# Arduino_shield.net
KiCad netlist of a schematic drawn in EAGLE
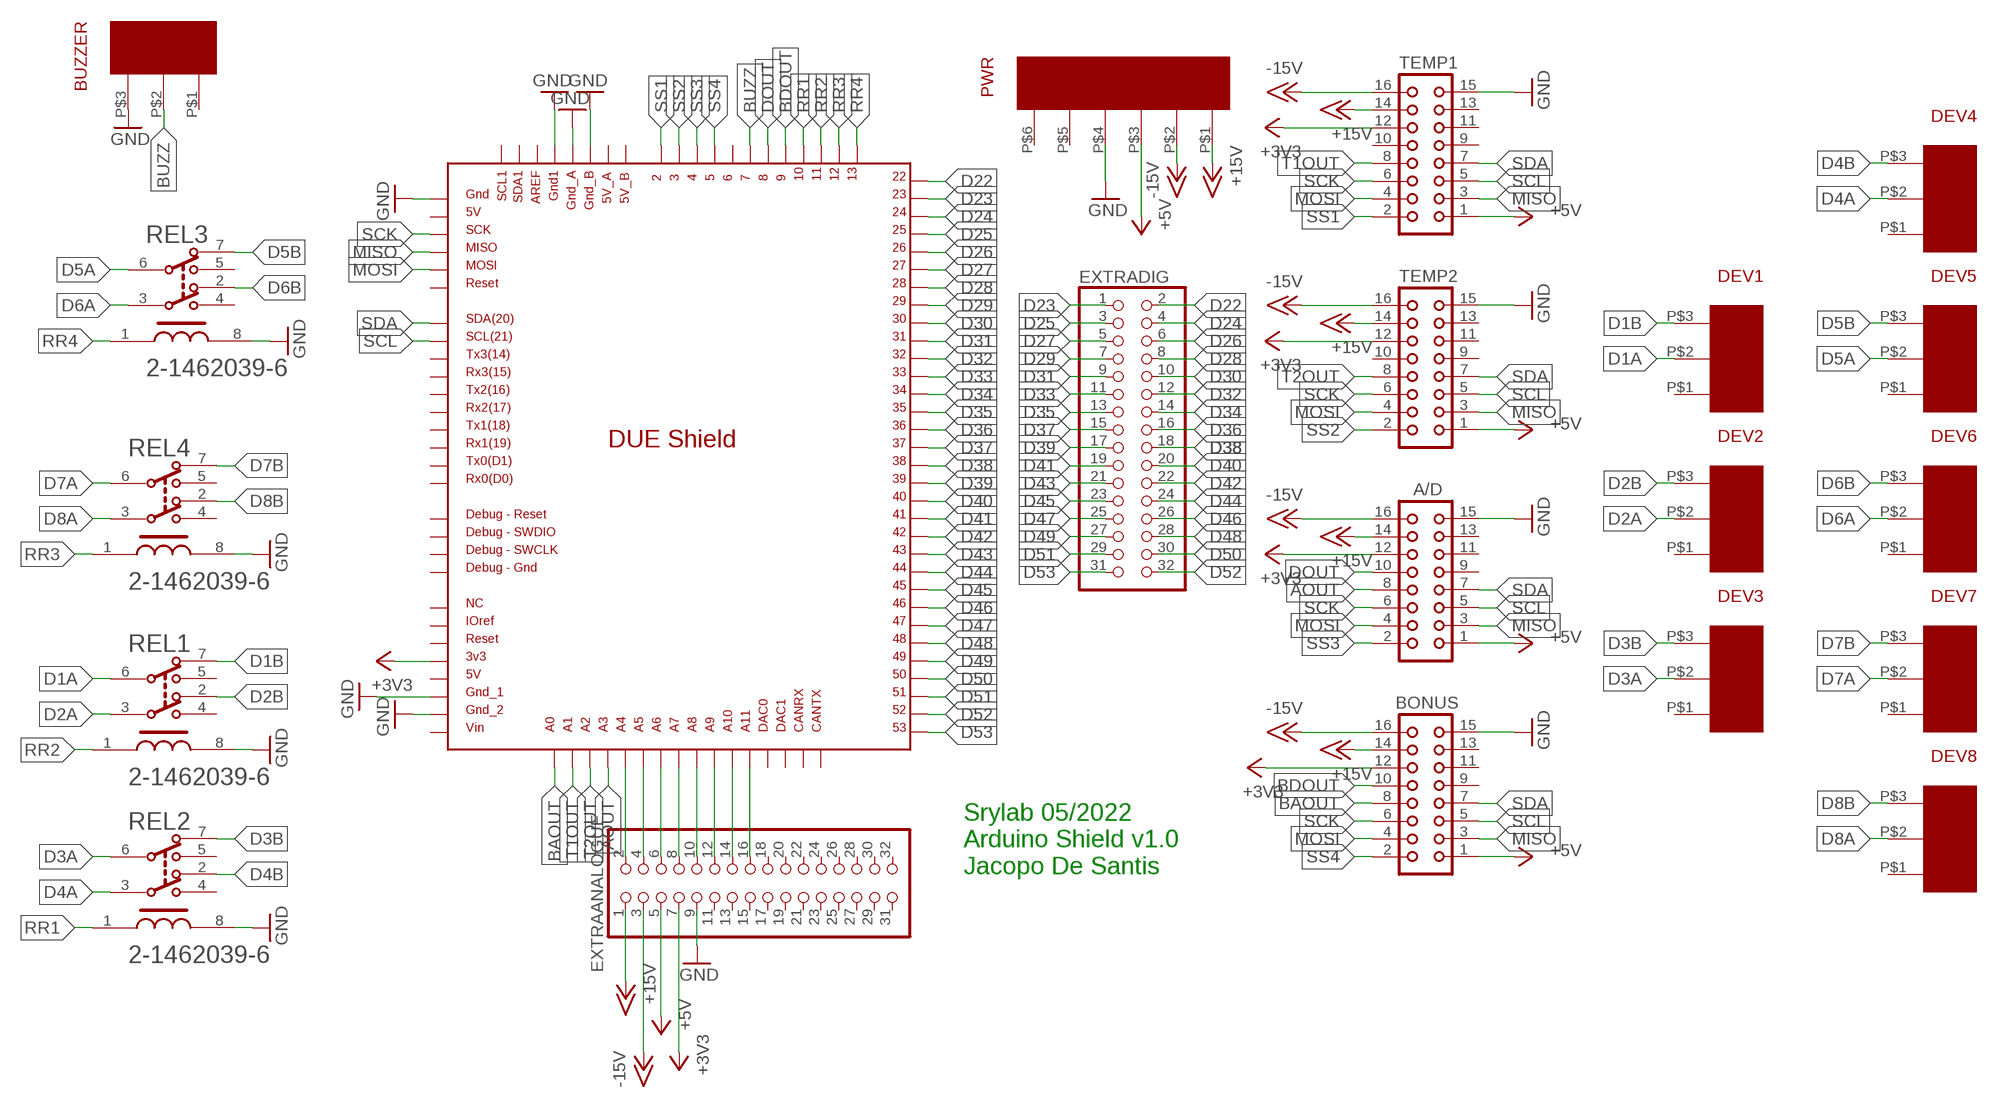
[diagram p0: schematic, sheet 1]

(export (version "E")
  (design (tool "Eeschema 10.0.6"))
  (components
    (comp (ref "A/D")
      (value "CON16L")
      (footprint "eagle-import:CON16L")
      (libsource (lib "eagle-import") (part "CON16L"))
    )
    (comp (ref "BONUS")
      (value "CON16L")
      (footprint "eagle-import:CON16L")
      (libsource (lib "eagle-import") (part "CON16L"))
    )
    (comp (ref "BUZZER")
      (value "3PIN_CON")
      (footprint "eagle-import:3PIN_CON")
      (libsource (lib "eagle-import") (part "3PIN_CON"))
    )
    (comp (ref "DEV1")
      (value "3PIN_CON")
      (footprint "eagle-import:3PIN_CON")
      (libsource (lib "eagle-import") (part "3PIN_CON"))
    )
    (comp (ref "DEV2")
      (value "3PIN_CON")
      (footprint "eagle-import:3PIN_CON")
      (libsource (lib "eagle-import") (part "3PIN_CON"))
    )
    (comp (ref "DEV3")
      (value "3PIN_CON")
      (footprint "eagle-import:3PIN_CON")
      (libsource (lib "eagle-import") (part "3PIN_CON"))
    )
    (comp (ref "DEV4")
      (value "3PIN_CON")
      (footprint "eagle-import:3PIN_CON")
      (libsource (lib "eagle-import") (part "3PIN_CON"))
    )
    (comp (ref "DEV5")
      (value "3PIN_CON")
      (footprint "eagle-import:3PIN_CON")
      (libsource (lib "eagle-import") (part "3PIN_CON"))
    )
    (comp (ref "DEV6")
      (value "3PIN_CON")
      (footprint "eagle-import:3PIN_CON")
      (libsource (lib "eagle-import") (part "3PIN_CON"))
    )
    (comp (ref "DEV7")
      (value "3PIN_CON")
      (footprint "eagle-import:3PIN_CON")
      (libsource (lib "eagle-import") (part "3PIN_CON"))
    )
    (comp (ref "DEV8")
      (value "3PIN_CON")
      (footprint "eagle-import:3PIN_CON")
      (libsource (lib "eagle-import") (part "3PIN_CON"))
    )
    (comp (ref "EXTRAANALOGUE")
      (value "PINHD-2X16")
      (footprint "eagle-import:2X16")
      (libsource (lib "eagle-import") (part "PINHD-2X16"))
    )
    (comp (ref "EXTRADIG")
      (value "PINHD-2X16")
      (footprint "eagle-import:2X16")
      (libsource (lib "eagle-import") (part "PINHD-2X16"))
    )
    (comp (ref "PWR")
      (value "6PIN_CON")
      (footprint "eagle-import:6PIN_CON")
      (libsource (lib "eagle-import") (part "6PIN_CON"))
    )
    (comp (ref "REL1")
      (value "TE_2-1462039-6TE_2-1462039-6_0_0")
      (footprint "eagle-import:TE_2-1462039-6_0")
      (fields
        (field (name "DIGIKEY_PART_NUMBER") "PB1163CT-ND")
        (field (name "MF") "TE")
        (field (name "MOUSER_PART_NUMBER") "655-IM21GR")
      )
      (libsource (lib "eagle-import") (part "TE_2-1462039-6TE_2-1462039-6_0_0"))
    )
    (comp (ref "REL2")
      (value "TE_2-1462039-6TE_2-1462039-6_0_0")
      (footprint "eagle-import:TE_2-1462039-6_0")
      (fields
        (field (name "DIGIKEY_PART_NUMBER") "PB1163CT-ND")
        (field (name "MF") "TE")
        (field (name "MOUSER_PART_NUMBER") "655-IM21GR")
      )
      (libsource (lib "eagle-import") (part "TE_2-1462039-6TE_2-1462039-6_0_0"))
    )
    (comp (ref "REL3")
      (value "TE_2-1462039-6TE_2-1462039-6_0_0")
      (footprint "eagle-import:TE_2-1462039-6_0")
      (fields
        (field (name "DIGIKEY_PART_NUMBER") "PB1163CT-ND")
        (field (name "MF") "TE")
        (field (name "MOUSER_PART_NUMBER") "655-IM21GR")
      )
      (libsource (lib "eagle-import") (part "TE_2-1462039-6TE_2-1462039-6_0_0"))
    )
    (comp (ref "REL4")
      (value "TE_2-1462039-6TE_2-1462039-6_0_0")
      (footprint "eagle-import:TE_2-1462039-6_0")
      (fields
        (field (name "DIGIKEY_PART_NUMBER") "PB1163CT-ND")
        (field (name "MF") "TE")
        (field (name "MOUSER_PART_NUMBER") "655-IM21GR")
      )
      (libsource (lib "eagle-import") (part "TE_2-1462039-6TE_2-1462039-6_0_0"))
    )
    (comp (ref "TEMP1")
      (value "CON16L")
      (footprint "eagle-import:CON16L")
      (libsource (lib "eagle-import") (part "CON16L"))
    )
    (comp (ref "TEMP2")
      (value "CON16L")
      (footprint "eagle-import:CON16L")
      (libsource (lib "eagle-import") (part "CON16L"))
    )
    (comp (ref "U$1")
      (value "DUE(NORMAL)")
      (footprint "eagle-import:DUE(NORMAL)")
      (libsource (lib "eagle-import") (part "DUE(NORMAL)"))
    )
  )
  (nets
    (net (code "1") (name "+3V3") (class "Default")
      (node (ref "A/D") (pin "12") (pinfunction "12_12") (pintype "passive"))
      (node (ref "BONUS") (pin "12") (pinfunction "12_12") (pintype "passive"))
      (node (ref "EXTRAANALOGUE") (pin "7") (pinfunction "7_7") (pintype "passive"))
      (node (ref "TEMP1") (pin "12") (pinfunction "12_12") (pintype "passive"))
      (node (ref "TEMP2") (pin "12") (pinfunction "12_12") (pintype "passive"))
      (node (ref "U$1") (pin "3V3") (pinfunction "3V3_3V3") (pintype "bidirectional"))
    )
    (net (code "2") (name "+5V") (class "Default")
      (node (ref "A/D") (pin "1") (pinfunction "1_1") (pintype "passive"))
      (node (ref "BONUS") (pin "1") (pinfunction "1_1") (pintype "passive"))
      (node (ref "EXTRAANALOGUE") (pin "5") (pinfunction "5_5") (pintype "passive"))
      (node (ref "PWR") (pin "P$3") (pinfunction "P$3_P$3") (pintype "bidirectional"))
      (node (ref "TEMP1") (pin "1") (pinfunction "1_1") (pintype "passive"))
      (node (ref "TEMP2") (pin "1") (pinfunction "1_1") (pintype "passive"))
    )
    (net (code "3") (name "+15V") (class "Default")
      (node (ref "A/D") (pin "14") (pinfunction "14_14") (pintype "passive"))
      (node (ref "BONUS") (pin "14") (pinfunction "14_14") (pintype "passive"))
      (node (ref "EXTRAANALOGUE") (pin "1") (pinfunction "1_1") (pintype "passive"))
      (node (ref "PWR") (pin "P$1") (pinfunction "P$1_P$1") (pintype "bidirectional"))
      (node (ref "TEMP1") (pin "14") (pinfunction "14_14") (pintype "passive"))
      (node (ref "TEMP2") (pin "14") (pinfunction "14_14") (pintype "passive"))
    )
    (net (code "4") (name "-15V") (class "Default")
      (node (ref "A/D") (pin "16") (pinfunction "16_16") (pintype "passive"))
      (node (ref "BONUS") (pin "16") (pinfunction "16_16") (pintype "passive"))
      (node (ref "EXTRAANALOGUE") (pin "3") (pinfunction "3_3") (pintype "passive"))
      (node (ref "PWR") (pin "P$2") (pinfunction "P$2_P$2") (pintype "bidirectional"))
      (node (ref "TEMP1") (pin "16") (pinfunction "16_16") (pintype "passive"))
      (node (ref "TEMP2") (pin "16") (pinfunction "16_16") (pintype "passive"))
    )
    (net (code "5") (name "AOUT") (class "Default")
      (node (ref "A/D") (pin "8") (pinfunction "8_8") (pintype "passive"))
      (node (ref "U$1") (pin "A3") (pinfunction "A3_A3") (pintype "bidirectional"))
    )
    (net (code "6") (name "BAOUT") (class "Default")
      (node (ref "BONUS") (pin "8") (pinfunction "8_8") (pintype "passive"))
      (node (ref "U$1") (pin "A0") (pinfunction "A0_A0") (pintype "bidirectional"))
    )
    (net (code "7") (name "BDOUT") (class "Default")
      (node (ref "BONUS") (pin "10") (pinfunction "10_10") (pintype "passive"))
      (node (ref "U$1") (pin "9") (pinfunction "9_9") (pintype "bidirectional"))
    )
    (net (code "8") (name "BUZZ") (class "Default")
      (node (ref "BUZZER") (pin "P$2") (pinfunction "P$2_P$2") (pintype "bidirectional"))
      (node (ref "U$1") (pin "7") (pinfunction "7_7") (pintype "bidirectional"))
    )
    (net (code "9") (name "D1A") (class "Default")
      (node (ref "DEV1") (pin "P$2") (pinfunction "P$2_P$2") (pintype "bidirectional"))
      (node (ref "REL1") (pin "6") (pinfunction "6_6") (pintype "passive"))
    )
    (net (code "10") (name "D1B") (class "Default")
      (node (ref "DEV1") (pin "P$3") (pinfunction "P$3_P$3") (pintype "bidirectional"))
      (node (ref "REL1") (pin "7") (pinfunction "7_7") (pintype "passive"))
    )
    (net (code "11") (name "D2A") (class "Default")
      (node (ref "DEV2") (pin "P$2") (pinfunction "P$2_P$2") (pintype "bidirectional"))
      (node (ref "REL1") (pin "3") (pinfunction "3_3") (pintype "passive"))
    )
    (net (code "12") (name "D2B") (class "Default")
      (node (ref "DEV2") (pin "P$3") (pinfunction "P$3_P$3") (pintype "bidirectional"))
      (node (ref "REL1") (pin "2") (pinfunction "2_2") (pintype "passive"))
    )
    (net (code "13") (name "D3A") (class "Default")
      (node (ref "DEV3") (pin "P$2") (pinfunction "P$2_P$2") (pintype "bidirectional"))
      (node (ref "REL2") (pin "6") (pinfunction "6_6") (pintype "passive"))
    )
    (net (code "14") (name "D3B") (class "Default")
      (node (ref "DEV3") (pin "P$3") (pinfunction "P$3_P$3") (pintype "bidirectional"))
      (node (ref "REL2") (pin "7") (pinfunction "7_7") (pintype "passive"))
    )
    (net (code "15") (name "D4A") (class "Default")
      (node (ref "DEV4") (pin "P$2") (pinfunction "P$2_P$2") (pintype "bidirectional"))
      (node (ref "REL2") (pin "3") (pinfunction "3_3") (pintype "passive"))
    )
    (net (code "16") (name "D4B") (class "Default")
      (node (ref "DEV4") (pin "P$3") (pinfunction "P$3_P$3") (pintype "bidirectional"))
      (node (ref "REL2") (pin "2") (pinfunction "2_2") (pintype "passive"))
    )
    (net (code "17") (name "D5A") (class "Default")
      (node (ref "DEV5") (pin "P$2") (pinfunction "P$2_P$2") (pintype "bidirectional"))
      (node (ref "REL3") (pin "6") (pinfunction "6_6") (pintype "passive"))
    )
    (net (code "18") (name "D5B") (class "Default")
      (node (ref "DEV5") (pin "P$3") (pinfunction "P$3_P$3") (pintype "bidirectional"))
      (node (ref "REL3") (pin "7") (pinfunction "7_7") (pintype "passive"))
    )
    (net (code "19") (name "D6A") (class "Default")
      (node (ref "DEV6") (pin "P$2") (pinfunction "P$2_P$2") (pintype "bidirectional"))
      (node (ref "REL3") (pin "3") (pinfunction "3_3") (pintype "passive"))
    )
    (net (code "20") (name "D6B") (class "Default")
      (node (ref "DEV6") (pin "P$3") (pinfunction "P$3_P$3") (pintype "bidirectional"))
      (node (ref "REL3") (pin "2") (pinfunction "2_2") (pintype "passive"))
    )
    (net (code "21") (name "D7A") (class "Default")
      (node (ref "DEV7") (pin "P$2") (pinfunction "P$2_P$2") (pintype "bidirectional"))
      (node (ref "REL4") (pin "6") (pinfunction "6_6") (pintype "passive"))
    )
    (net (code "22") (name "D7B") (class "Default")
      (node (ref "DEV7") (pin "P$3") (pinfunction "P$3_P$3") (pintype "bidirectional"))
      (node (ref "REL4") (pin "7") (pinfunction "7_7") (pintype "passive"))
    )
    (net (code "23") (name "D8A") (class "Default")
      (node (ref "DEV8") (pin "P$2") (pinfunction "P$2_P$2") (pintype "bidirectional"))
      (node (ref "REL4") (pin "3") (pinfunction "3_3") (pintype "passive"))
    )
    (net (code "24") (name "D8B") (class "Default")
      (node (ref "DEV8") (pin "P$3") (pinfunction "P$3_P$3") (pintype "bidirectional"))
      (node (ref "REL4") (pin "2") (pinfunction "2_2") (pintype "passive"))
    )
    (net (code "25") (name "D22") (class "Default")
      (node (ref "EXTRADIG") (pin "2") (pinfunction "2_2") (pintype "passive"))
      (node (ref "U$1") (pin "22") (pinfunction "22_22") (pintype "bidirectional"))
    )
    (net (code "26") (name "D23") (class "Default")
      (node (ref "EXTRADIG") (pin "1") (pinfunction "1_1") (pintype "passive"))
      (node (ref "U$1") (pin "23") (pinfunction "23_23") (pintype "bidirectional"))
    )
    (net (code "27") (name "D24") (class "Default")
      (node (ref "EXTRADIG") (pin "4") (pinfunction "4_4") (pintype "passive"))
      (node (ref "U$1") (pin "24") (pinfunction "24_24") (pintype "bidirectional"))
    )
    (net (code "28") (name "D25") (class "Default")
      (node (ref "EXTRADIG") (pin "3") (pinfunction "3_3") (pintype "passive"))
      (node (ref "U$1") (pin "25") (pinfunction "25_25") (pintype "bidirectional"))
    )
    (net (code "29") (name "D26") (class "Default")
      (node (ref "EXTRADIG") (pin "6") (pinfunction "6_6") (pintype "passive"))
      (node (ref "U$1") (pin "26") (pinfunction "26_26") (pintype "bidirectional"))
    )
    (net (code "30") (name "D27") (class "Default")
      (node (ref "EXTRADIG") (pin "5") (pinfunction "5_5") (pintype "passive"))
      (node (ref "U$1") (pin "27") (pinfunction "27_27") (pintype "bidirectional"))
    )
    (net (code "31") (name "D28") (class "Default")
      (node (ref "EXTRADIG") (pin "8") (pinfunction "8_8") (pintype "passive"))
      (node (ref "U$1") (pin "28") (pinfunction "28_28") (pintype "bidirectional"))
    )
    (net (code "32") (name "D29") (class "Default")
      (node (ref "EXTRADIG") (pin "7") (pinfunction "7_7") (pintype "passive"))
      (node (ref "U$1") (pin "29") (pinfunction "29_29") (pintype "bidirectional"))
    )
    (net (code "33") (name "D30") (class "Default")
      (node (ref "EXTRADIG") (pin "10") (pinfunction "10_10") (pintype "passive"))
      (node (ref "U$1") (pin "30") (pinfunction "30_30") (pintype "bidirectional"))
    )
    (net (code "34") (name "D31") (class "Default")
      (node (ref "EXTRADIG") (pin "9") (pinfunction "9_9") (pintype "passive"))
      (node (ref "U$1") (pin "31") (pinfunction "31_31") (pintype "bidirectional"))
    )
    (net (code "35") (name "D32") (class "Default")
      (node (ref "EXTRADIG") (pin "12") (pinfunction "12_12") (pintype "passive"))
      (node (ref "U$1") (pin "32") (pinfunction "32_32") (pintype "bidirectional"))
    )
    (net (code "36") (name "D33") (class "Default")
      (node (ref "EXTRADIG") (pin "11") (pinfunction "11_11") (pintype "passive"))
      (node (ref "U$1") (pin "33") (pinfunction "33_33") (pintype "bidirectional"))
    )
    (net (code "37") (name "D34") (class "Default")
      (node (ref "EXTRADIG") (pin "14") (pinfunction "14_14") (pintype "passive"))
      (node (ref "U$1") (pin "34") (pinfunction "34_34") (pintype "bidirectional"))
    )
    (net (code "38") (name "D35") (class "Default")
      (node (ref "EXTRADIG") (pin "13") (pinfunction "13_13") (pintype "passive"))
      (node (ref "U$1") (pin "35") (pinfunction "35_35") (pintype "bidirectional"))
    )
    (net (code "39") (name "D36") (class "Default")
      (node (ref "EXTRADIG") (pin "16") (pinfunction "16_16") (pintype "passive"))
      (node (ref "U$1") (pin "36") (pinfunction "36_36") (pintype "bidirectional"))
    )
    (net (code "40") (name "D37") (class "Default")
      (node (ref "EXTRADIG") (pin "15") (pinfunction "15_15") (pintype "passive"))
      (node (ref "U$1") (pin "37") (pinfunction "37_37") (pintype "bidirectional"))
    )
    (net (code "41") (name "D38") (class "Default")
      (node (ref "EXTRADIG") (pin "18") (pinfunction "18_18") (pintype "passive"))
      (node (ref "U$1") (pin "38") (pinfunction "38_38") (pintype "bidirectional"))
    )
    (net (code "42") (name "D39") (class "Default")
      (node (ref "EXTRADIG") (pin "17") (pinfunction "17_17") (pintype "passive"))
      (node (ref "U$1") (pin "39") (pinfunction "39_39") (pintype "bidirectional"))
    )
    (net (code "43") (name "D40") (class "Default")
      (node (ref "EXTRADIG") (pin "20") (pinfunction "20_20") (pintype "passive"))
      (node (ref "U$1") (pin "40") (pinfunction "40_40") (pintype "bidirectional"))
    )
    (net (code "44") (name "D41") (class "Default")
      (node (ref "EXTRADIG") (pin "19") (pinfunction "19_19") (pintype "passive"))
      (node (ref "U$1") (pin "41") (pinfunction "41_41") (pintype "bidirectional"))
    )
    (net (code "45") (name "D42") (class "Default")
      (node (ref "EXTRADIG") (pin "22") (pinfunction "22_22") (pintype "passive"))
      (node (ref "U$1") (pin "42") (pinfunction "42_42") (pintype "bidirectional"))
    )
    (net (code "46") (name "D43") (class "Default")
      (node (ref "EXTRADIG") (pin "21") (pinfunction "21_21") (pintype "passive"))
      (node (ref "U$1") (pin "43") (pinfunction "43_43") (pintype "bidirectional"))
    )
    (net (code "47") (name "D44") (class "Default")
      (node (ref "EXTRADIG") (pin "24") (pinfunction "24_24") (pintype "passive"))
      (node (ref "U$1") (pin "44") (pinfunction "44_44") (pintype "bidirectional"))
    )
    (net (code "48") (name "D45") (class "Default")
      (node (ref "EXTRADIG") (pin "23") (pinfunction "23_23") (pintype "passive"))
      (node (ref "U$1") (pin "45") (pinfunction "45_45") (pintype "bidirectional"))
    )
    (net (code "49") (name "D46") (class "Default")
      (node (ref "EXTRADIG") (pin "26") (pinfunction "26_26") (pintype "passive"))
      (node (ref "U$1") (pin "46") (pinfunction "46_46") (pintype "bidirectional"))
    )
    (net (code "50") (name "D47") (class "Default")
      (node (ref "EXTRADIG") (pin "25") (pinfunction "25_25") (pintype "passive"))
      (node (ref "U$1") (pin "47") (pinfunction "47_47") (pintype "bidirectional"))
    )
    (net (code "51") (name "D48") (class "Default")
      (node (ref "EXTRADIG") (pin "28") (pinfunction "28_28") (pintype "passive"))
      (node (ref "U$1") (pin "48") (pinfunction "48_48") (pintype "bidirectional"))
    )
    (net (code "52") (name "D49") (class "Default")
      (node (ref "EXTRADIG") (pin "27") (pinfunction "27_27") (pintype "passive"))
      (node (ref "U$1") (pin "49") (pinfunction "49_49") (pintype "bidirectional"))
    )
    (net (code "53") (name "D50") (class "Default")
      (node (ref "EXTRADIG") (pin "30") (pinfunction "30_30") (pintype "passive"))
      (node (ref "U$1") (pin "50") (pinfunction "50_50") (pintype "bidirectional"))
    )
    (net (code "54") (name "D51") (class "Default")
      (node (ref "EXTRADIG") (pin "29") (pinfunction "29_29") (pintype "passive"))
      (node (ref "U$1") (pin "51") (pinfunction "51_51") (pintype "bidirectional"))
    )
    (net (code "55") (name "D52") (class "Default")
      (node (ref "EXTRADIG") (pin "32") (pinfunction "32_32") (pintype "passive"))
      (node (ref "U$1") (pin "52") (pinfunction "52_52") (pintype "bidirectional"))
    )
    (net (code "56") (name "D53") (class "Default")
      (node (ref "EXTRADIG") (pin "31") (pinfunction "31_31") (pintype "passive"))
      (node (ref "U$1") (pin "53") (pinfunction "53_53") (pintype "bidirectional"))
    )
    (net (code "57") (name "DOUT") (class "Default")
      (node (ref "A/D") (pin "10") (pinfunction "10_10") (pintype "passive"))
      (node (ref "U$1") (pin "8") (pinfunction "8_8") (pintype "bidirectional"))
    )
    (net (code "58") (name "GND") (class "Default")
      (node (ref "A/D") (pin "15") (pinfunction "15_15") (pintype "passive"))
      (node (ref "BONUS") (pin "15") (pinfunction "15_15") (pintype "passive"))
      (node (ref "BUZZER") (pin "P$3") (pinfunction "P$3_P$3") (pintype "bidirectional"))
      (node (ref "EXTRAANALOGUE") (pin "9") (pinfunction "9_9") (pintype "passive"))
      (node (ref "PWR") (pin "P$4") (pinfunction "P$4_P$4") (pintype "bidirectional"))
      (node (ref "REL1") (pin "8") (pinfunction "8_8") (pintype "passive"))
      (node (ref "REL2") (pin "8") (pinfunction "8_8") (pintype "passive"))
      (node (ref "REL3") (pin "8") (pinfunction "8_8") (pintype "passive"))
      (node (ref "REL4") (pin "8") (pinfunction "8_8") (pintype "passive"))
      (node (ref "TEMP1") (pin "15") (pinfunction "15_15") (pintype "passive"))
      (node (ref "TEMP2") (pin "15") (pinfunction "15_15") (pintype "passive"))
      (node (ref "U$1") (pin "5V_ICSP") (pinfunction "5V_ICSP_5V_ICSP") (pintype "bidirectional"))
      (node (ref "U$1") (pin "GND1") (pinfunction "GND1_GND1") (pintype "bidirectional"))
      (node (ref "U$1") (pin "GND_1") (pinfunction "GND_1_GND_1") (pintype "bidirectional"))
      (node (ref "U$1") (pin "GND_2") (pinfunction "GND_2_GND_2") (pintype "bidirectional"))
      (node (ref "U$1") (pin "GND_A") (pinfunction "GND_A_GND_A") (pintype "bidirectional"))
      (node (ref "U$1") (pin "GND_B") (pinfunction "GND_B_GND_B") (pintype "bidirectional"))
    )
    (net (code "59") (name "MISO") (class "Default")
      (node (ref "A/D") (pin "3") (pinfunction "3_3") (pintype "passive"))
      (node (ref "BONUS") (pin "3") (pinfunction "3_3") (pintype "passive"))
      (node (ref "TEMP1") (pin "3") (pinfunction "3_3") (pintype "passive"))
      (node (ref "TEMP2") (pin "3") (pinfunction "3_3") (pintype "passive"))
      (node (ref "U$1") (pin "MISO_ICSP") (pinfunction "MISO_ICSP_MISO_ICSP") (pintype "bidirectional"))
    )
    (net (code "60") (name "MOSI") (class "Default")
      (node (ref "A/D") (pin "4") (pinfunction "4_4") (pintype "passive"))
      (node (ref "BONUS") (pin "4") (pinfunction "4_4") (pintype "passive"))
      (node (ref "TEMP1") (pin "4") (pinfunction "4_4") (pintype "passive"))
      (node (ref "TEMP2") (pin "4") (pinfunction "4_4") (pintype "passive"))
      (node (ref "U$1") (pin "MOSI_ICSP") (pinfunction "MOSI_ICSP_MOSI_ICSP") (pintype "bidirectional"))
    )
    (net (code "61") (name "Net-(EXTRAANALOGUE-Pad2)") (class "Default")
      (node (ref "EXTRAANALOGUE") (pin "2") (pinfunction "2_2") (pintype "passive"))
      (node (ref "U$1") (pin "A4") (pinfunction "A4_A4") (pintype "bidirectional"))
    )
    (net (code "62") (name "Net-(EXTRAANALOGUE-Pad4)") (class "Default")
      (node (ref "EXTRAANALOGUE") (pin "4") (pinfunction "4_4") (pintype "passive"))
      (node (ref "U$1") (pin "A5") (pinfunction "A5_A5") (pintype "bidirectional"))
    )
    (net (code "63") (name "Net-(EXTRAANALOGUE-Pad6)") (class "Default")
      (node (ref "EXTRAANALOGUE") (pin "6") (pinfunction "6_6") (pintype "passive"))
      (node (ref "U$1") (pin "A6") (pinfunction "A6_A6") (pintype "bidirectional"))
    )
    (net (code "64") (name "Net-(EXTRAANALOGUE-Pad8)") (class "Default")
      (node (ref "EXTRAANALOGUE") (pin "8") (pinfunction "8_8") (pintype "passive"))
      (node (ref "U$1") (pin "A7") (pinfunction "A7_A7") (pintype "bidirectional"))
    )
    (net (code "65") (name "Net-(EXTRAANALOGUE-Pad10)") (class "Default")
      (node (ref "EXTRAANALOGUE") (pin "10") (pinfunction "10_10") (pintype "passive"))
      (node (ref "U$1") (pin "A8") (pinfunction "A8_A8") (pintype "bidirectional"))
    )
    (net (code "66") (name "Net-(EXTRAANALOGUE-Pad12)") (class "Default")
      (node (ref "EXTRAANALOGUE") (pin "12") (pinfunction "12_12") (pintype "passive"))
      (node (ref "U$1") (pin "A9") (pinfunction "A9_A9") (pintype "bidirectional"))
    )
    (net (code "67") (name "Net-(EXTRAANALOGUE-Pad14)") (class "Default")
      (node (ref "EXTRAANALOGUE") (pin "14") (pinfunction "14_14") (pintype "passive"))
      (node (ref "U$1") (pin "A10") (pinfunction "A10_A10") (pintype "bidirectional"))
    )
    (net (code "68") (name "Net-(EXTRAANALOGUE-Pad16)") (class "Default")
      (node (ref "EXTRAANALOGUE") (pin "16") (pinfunction "16_16") (pintype "passive"))
      (node (ref "U$1") (pin "A11") (pinfunction "A11_A11") (pintype "bidirectional"))
    )
    (net (code "69") (name "RR1") (class "Default")
      (node (ref "REL2") (pin "1") (pinfunction "1_1") (pintype "passive"))
      (node (ref "U$1") (pin "10") (pinfunction "10_10") (pintype "bidirectional"))
    )
    (net (code "70") (name "RR2") (class "Default")
      (node (ref "REL1") (pin "1") (pinfunction "1_1") (pintype "passive"))
      (node (ref "U$1") (pin "11") (pinfunction "11_11") (pintype "bidirectional"))
    )
    (net (code "71") (name "RR3") (class "Default")
      (node (ref "REL4") (pin "1") (pinfunction "1_1") (pintype "passive"))
      (node (ref "U$1") (pin "12") (pinfunction "12_12") (pintype "bidirectional"))
    )
    (net (code "72") (name "RR4") (class "Default")
      (node (ref "REL3") (pin "1") (pinfunction "1_1") (pintype "passive"))
      (node (ref "U$1") (pin "13") (pinfunction "13_13") (pintype "bidirectional"))
    )
    (net (code "73") (name "SCK") (class "Default")
      (node (ref "A/D") (pin "6") (pinfunction "6_6") (pintype "passive"))
      (node (ref "BONUS") (pin "6") (pinfunction "6_6") (pintype "passive"))
      (node (ref "TEMP1") (pin "6") (pinfunction "6_6") (pintype "passive"))
      (node (ref "TEMP2") (pin "6") (pinfunction "6_6") (pintype "passive"))
      (node (ref "U$1") (pin "SCK_ICSP") (pinfunction "SCK_ICSP_SCK_ICSP") (pintype "bidirectional"))
    )
    (net (code "74") (name "SCL") (class "Default")
      (node (ref "A/D") (pin "5") (pinfunction "5_5") (pintype "passive"))
      (node (ref "BONUS") (pin "5") (pinfunction "5_5") (pintype "passive"))
      (node (ref "TEMP1") (pin "5") (pinfunction "5_5") (pintype "passive"))
      (node (ref "TEMP2") (pin "5") (pinfunction "5_5") (pintype "passive"))
      (node (ref "U$1") (pin "SCL") (pinfunction "SCL_SCL") (pintype "bidirectional"))
    )
    (net (code "75") (name "SDA") (class "Default")
      (node (ref "A/D") (pin "7") (pinfunction "7_7") (pintype "passive"))
      (node (ref "BONUS") (pin "7") (pinfunction "7_7") (pintype "passive"))
      (node (ref "TEMP1") (pin "7") (pinfunction "7_7") (pintype "passive"))
      (node (ref "TEMP2") (pin "7") (pinfunction "7_7") (pintype "passive"))
      (node (ref "U$1") (pin "SDA") (pinfunction "SDA_SDA") (pintype "bidirectional"))
    )
    (net (code "76") (name "SS1") (class "Default")
      (node (ref "TEMP1") (pin "2") (pinfunction "2_2") (pintype "passive"))
      (node (ref "U$1") (pin "2") (pinfunction "2_2") (pintype "bidirectional"))
    )
    (net (code "77") (name "SS2") (class "Default")
      (node (ref "TEMP2") (pin "2") (pinfunction "2_2") (pintype "passive"))
      (node (ref "U$1") (pin "3") (pinfunction "3_3") (pintype "bidirectional"))
    )
    (net (code "78") (name "SS3") (class "Default")
      (node (ref "A/D") (pin "2") (pinfunction "2_2") (pintype "passive"))
      (node (ref "U$1") (pin "4") (pinfunction "4_4") (pintype "bidirectional"))
    )
    (net (code "79") (name "SS4") (class "Default")
      (node (ref "BONUS") (pin "2") (pinfunction "2_2") (pintype "passive"))
      (node (ref "U$1") (pin "5") (pinfunction "5_5") (pintype "bidirectional"))
    )
    (net (code "80") (name "T1OUT") (class "Default")
      (node (ref "TEMP1") (pin "8") (pinfunction "8_8") (pintype "passive"))
      (node (ref "U$1") (pin "A1") (pinfunction "A1_A1") (pintype "bidirectional"))
    )
    (net (code "81") (name "T2OUT") (class "Default")
      (node (ref "TEMP2") (pin "8") (pinfunction "8_8") (pintype "passive"))
      (node (ref "U$1") (pin "A2") (pinfunction "A2_A2") (pintype "bidirectional"))
    )
    (net (code "82") (name "unconnected-(A/D-Pad9)") (class "Default")
      (node (ref "A/D") (pin "9") (pinfunction "9_9") (pintype "passive"))
    )
    (net (code "83") (name "unconnected-(A/D-Pad11)") (class "Default")
      (node (ref "A/D") (pin "11") (pinfunction "11_11") (pintype "passive"))
    )
    (net (code "84") (name "unconnected-(A/D-Pad13)") (class "Default")
      (node (ref "A/D") (pin "13") (pinfunction "13_13") (pintype "passive"))
    )
    (net (code "85") (name "unconnected-(BONUS-Pad9)") (class "Default")
      (node (ref "BONUS") (pin "9") (pinfunction "9_9") (pintype "passive"))
    )
    (net (code "86") (name "unconnected-(BONUS-Pad11)") (class "Default")
      (node (ref "BONUS") (pin "11") (pinfunction "11_11") (pintype "passive"))
    )
    (net (code "87") (name "unconnected-(BONUS-Pad13)") (class "Default")
      (node (ref "BONUS") (pin "13") (pinfunction "13_13") (pintype "passive"))
    )
    (net (code "88") (name "unconnected-(BUZZER-PadP$1)") (class "Default")
      (node (ref "BUZZER") (pin "P$1") (pinfunction "P$1_P$1") (pintype "bidirectional"))
    )
    (net (code "89") (name "unconnected-(DEV1-PadP$1)") (class "Default")
      (node (ref "DEV1") (pin "P$1") (pinfunction "P$1_P$1") (pintype "bidirectional"))
    )
    (net (code "90") (name "unconnected-(DEV2-PadP$1)") (class "Default")
      (node (ref "DEV2") (pin "P$1") (pinfunction "P$1_P$1") (pintype "bidirectional"))
    )
    (net (code "91") (name "unconnected-(DEV3-PadP$1)") (class "Default")
      (node (ref "DEV3") (pin "P$1") (pinfunction "P$1_P$1") (pintype "bidirectional"))
    )
    (net (code "92") (name "unconnected-(DEV4-PadP$1)") (class "Default")
      (node (ref "DEV4") (pin "P$1") (pinfunction "P$1_P$1") (pintype "bidirectional"))
    )
    (net (code "93") (name "unconnected-(DEV5-PadP$1)") (class "Default")
      (node (ref "DEV5") (pin "P$1") (pinfunction "P$1_P$1") (pintype "bidirectional"))
    )
    (net (code "94") (name "unconnected-(DEV6-PadP$1)") (class "Default")
      (node (ref "DEV6") (pin "P$1") (pinfunction "P$1_P$1") (pintype "bidirectional"))
    )
    (net (code "95") (name "unconnected-(DEV7-PadP$1)") (class "Default")
      (node (ref "DEV7") (pin "P$1") (pinfunction "P$1_P$1") (pintype "bidirectional"))
    )
    (net (code "96") (name "unconnected-(DEV8-PadP$1)") (class "Default")
      (node (ref "DEV8") (pin "P$1") (pinfunction "P$1_P$1") (pintype "bidirectional"))
    )
    (net (code "97") (name "unconnected-(EXTRAANALOGUE-Pad11)") (class "Default")
      (node (ref "EXTRAANALOGUE") (pin "11") (pinfunction "11_11") (pintype "passive"))
    )
    (net (code "98") (name "unconnected-(EXTRAANALOGUE-Pad13)") (class "Default")
      (node (ref "EXTRAANALOGUE") (pin "13") (pinfunction "13_13") (pintype "passive"))
    )
    (net (code "99") (name "unconnected-(EXTRAANALOGUE-Pad15)") (class "Default")
      (node (ref "EXTRAANALOGUE") (pin "15") (pinfunction "15_15") (pintype "passive"))
    )
    (net (code "100") (name "unconnected-(EXTRAANALOGUE-Pad17)") (class "Default")
      (node (ref "EXTRAANALOGUE") (pin "17") (pinfunction "17_17") (pintype "passive"))
    )
    (net (code "101") (name "unconnected-(EXTRAANALOGUE-Pad18)") (class "Default")
      (node (ref "EXTRAANALOGUE") (pin "18") (pinfunction "18_18") (pintype "passive"))
    )
    (net (code "102") (name "unconnected-(EXTRAANALOGUE-Pad19)") (class "Default")
      (node (ref "EXTRAANALOGUE") (pin "19") (pinfunction "19_19") (pintype "passive"))
    )
    (net (code "103") (name "unconnected-(EXTRAANALOGUE-Pad20)") (class "Default")
      (node (ref "EXTRAANALOGUE") (pin "20") (pinfunction "20_20") (pintype "passive"))
    )
    (net (code "104") (name "unconnected-(EXTRAANALOGUE-Pad21)") (class "Default")
      (node (ref "EXTRAANALOGUE") (pin "21") (pinfunction "21_21") (pintype "passive"))
    )
    (net (code "105") (name "unconnected-(EXTRAANALOGUE-Pad22)") (class "Default")
      (node (ref "EXTRAANALOGUE") (pin "22") (pinfunction "22_22") (pintype "passive"))
    )
    (net (code "106") (name "unconnected-(EXTRAANALOGUE-Pad23)") (class "Default")
      (node (ref "EXTRAANALOGUE") (pin "23") (pinfunction "23_23") (pintype "passive"))
    )
    (net (code "107") (name "unconnected-(EXTRAANALOGUE-Pad24)") (class "Default")
      (node (ref "EXTRAANALOGUE") (pin "24") (pinfunction "24_24") (pintype "passive"))
    )
    (net (code "108") (name "unconnected-(EXTRAANALOGUE-Pad25)") (class "Default")
      (node (ref "EXTRAANALOGUE") (pin "25") (pinfunction "25_25") (pintype "passive"))
    )
    (net (code "109") (name "unconnected-(EXTRAANALOGUE-Pad26)") (class "Default")
      (node (ref "EXTRAANALOGUE") (pin "26") (pinfunction "26_26") (pintype "passive"))
    )
    (net (code "110") (name "unconnected-(EXTRAANALOGUE-Pad27)") (class "Default")
      (node (ref "EXTRAANALOGUE") (pin "27") (pinfunction "27_27") (pintype "passive"))
    )
    (net (code "111") (name "unconnected-(EXTRAANALOGUE-Pad28)") (class "Default")
      (node (ref "EXTRAANALOGUE") (pin "28") (pinfunction "28_28") (pintype "passive"))
    )
    (net (code "112") (name "unconnected-(EXTRAANALOGUE-Pad29)") (class "Default")
      (node (ref "EXTRAANALOGUE") (pin "29") (pinfunction "29_29") (pintype "passive"))
    )
    (net (code "113") (name "unconnected-(EXTRAANALOGUE-Pad30)") (class "Default")
      (node (ref "EXTRAANALOGUE") (pin "30") (pinfunction "30_30") (pintype "passive"))
    )
    (net (code "114") (name "unconnected-(EXTRAANALOGUE-Pad31)") (class "Default")
      (node (ref "EXTRAANALOGUE") (pin "31") (pinfunction "31_31") (pintype "passive"))
    )
    (net (code "115") (name "unconnected-(EXTRAANALOGUE-Pad32)") (class "Default")
      (node (ref "EXTRAANALOGUE") (pin "32") (pinfunction "32_32") (pintype "passive"))
    )
    (net (code "116") (name "unconnected-(PWR-PadP$5)") (class "Default")
      (node (ref "PWR") (pin "P$5") (pinfunction "P$5_P$5") (pintype "bidirectional"))
    )
    (net (code "117") (name "unconnected-(PWR-PadP$6)") (class "Default")
      (node (ref "PWR") (pin "P$6") (pinfunction "P$6_P$6") (pintype "bidirectional"))
    )
    (net (code "118") (name "unconnected-(REL1-Pad4)") (class "Default")
      (node (ref "REL1") (pin "4") (pinfunction "4_4") (pintype "passive"))
    )
    (net (code "119") (name "unconnected-(REL1-Pad5)") (class "Default")
      (node (ref "REL1") (pin "5") (pinfunction "5_5") (pintype "passive"))
    )
    (net (code "120") (name "unconnected-(REL2-Pad4)") (class "Default")
      (node (ref "REL2") (pin "4") (pinfunction "4_4") (pintype "passive"))
    )
    (net (code "121") (name "unconnected-(REL2-Pad5)") (class "Default")
      (node (ref "REL2") (pin "5") (pinfunction "5_5") (pintype "passive"))
    )
    (net (code "122") (name "unconnected-(REL3-Pad4)") (class "Default")
      (node (ref "REL3") (pin "4") (pinfunction "4_4") (pintype "passive"))
    )
    (net (code "123") (name "unconnected-(REL3-Pad5)") (class "Default")
      (node (ref "REL3") (pin "5") (pinfunction "5_5") (pintype "passive"))
    )
    (net (code "124") (name "unconnected-(REL4-Pad4)") (class "Default")
      (node (ref "REL4") (pin "4") (pinfunction "4_4") (pintype "passive"))
    )
    (net (code "125") (name "unconnected-(REL4-Pad5)") (class "Default")
      (node (ref "REL4") (pin "5") (pinfunction "5_5") (pintype "passive"))
    )
    (net (code "126") (name "unconnected-(TEMP1-Pad9)") (class "Default")
      (node (ref "TEMP1") (pin "9") (pinfunction "9_9") (pintype "passive"))
    )
    (net (code "127") (name "unconnected-(TEMP1-Pad10)") (class "Default")
      (node (ref "TEMP1") (pin "10") (pinfunction "10_10") (pintype "passive"))
    )
    (net (code "128") (name "unconnected-(TEMP1-Pad11)") (class "Default")
      (node (ref "TEMP1") (pin "11") (pinfunction "11_11") (pintype "passive"))
    )
    (net (code "129") (name "unconnected-(TEMP1-Pad13)") (class "Default")
      (node (ref "TEMP1") (pin "13") (pinfunction "13_13") (pintype "passive"))
    )
    (net (code "130") (name "unconnected-(TEMP2-Pad9)") (class "Default")
      (node (ref "TEMP2") (pin "9") (pinfunction "9_9") (pintype "passive"))
    )
    (net (code "131") (name "unconnected-(TEMP2-Pad10)") (class "Default")
      (node (ref "TEMP2") (pin "10") (pinfunction "10_10") (pintype "passive"))
    )
    (net (code "132") (name "unconnected-(TEMP2-Pad11)") (class "Default")
      (node (ref "TEMP2") (pin "11") (pinfunction "11_11") (pintype "passive"))
    )
    (net (code "133") (name "unconnected-(TEMP2-Pad13)") (class "Default")
      (node (ref "TEMP2") (pin "13") (pinfunction "13_13") (pintype "passive"))
    )
    (net (code "134") (name "unconnected-(U$1-Pad5V)") (class "Default")
      (node (ref "U$1") (pin "5V") (pinfunction "5V_5V") (pintype "bidirectional"))
    )
    (net (code "135") (name "unconnected-(U$1-Pad5V_A)") (class "Default")
      (node (ref "U$1") (pin "5V_A") (pinfunction "5V_A_5V_A") (pintype "bidirectional"))
    )
    (net (code "136") (name "unconnected-(U$1-Pad5V_B)") (class "Default")
      (node (ref "U$1") (pin "5V_B") (pinfunction "5V_B_5V_B") (pintype "bidirectional"))
    )
    (net (code "137") (name "unconnected-(U$1-Pad6)") (class "Default")
      (node (ref "U$1") (pin "6") (pinfunction "6_6") (pintype "bidirectional"))
    )
    (net (code "138") (name "unconnected-(U$1-PadAREF)") (class "Default")
      (node (ref "U$1") (pin "AREF") (pinfunction "AREF_AREF") (pintype "bidirectional"))
    )
    (net (code "139") (name "unconnected-(U$1-PadCANRX)") (class "Default")
      (node (ref "U$1") (pin "CANRX") (pinfunction "CANRX_CANRX") (pintype "bidirectional"))
    )
    (net (code "140") (name "unconnected-(U$1-PadCANTX)") (class "Default")
      (node (ref "U$1") (pin "CANTX") (pinfunction "CANTX_CANTX") (pintype "bidirectional"))
    )
    (net (code "141") (name "unconnected-(U$1-PadDAC0)") (class "Default")
      (node (ref "U$1") (pin "DAC0") (pinfunction "DAC0_DAC0") (pintype "bidirectional"))
    )
    (net (code "142") (name "unconnected-(U$1-PadDAC1)") (class "Default")
      (node (ref "U$1") (pin "DAC1") (pinfunction "DAC1_DAC1") (pintype "bidirectional"))
    )
    (net (code "143") (name "unconnected-(U$1-PadGND_DEBUG)") (class "Default")
      (node (ref "U$1") (pin "GND_DEBUG") (pinfunction "GND_DEBUG_GND_DEBUG") (pintype "bidirectional"))
    )
    (net (code "144") (name "unconnected-(U$1-PadGND_ICSP)") (class "Default")
      (node (ref "U$1") (pin "GND_ICSP") (pinfunction "GND_ICSP_GND_ICSP") (pintype "bidirectional"))
    )
    (net (code "145") (name "unconnected-(U$1-PadIOREF)") (class "Default")
      (node (ref "U$1") (pin "IOREF") (pinfunction "IOREF_IOREF") (pintype "bidirectional"))
    )
    (net (code "146") (name "unconnected-(U$1-PadNC)") (class "Default")
      (node (ref "U$1") (pin "NC") (pinfunction "NC_NC") (pintype "bidirectional"))
    )
    (net (code "147") (name "unconnected-(U$1-PadRESET)") (class "Default")
      (node (ref "U$1") (pin "RESET") (pinfunction "RESET_RESET") (pintype "bidirectional"))
    )
    (net (code "148") (name "unconnected-(U$1-PadRESET_DEBUG)") (class "Default")
      (node (ref "U$1") (pin "RESET_DEBUG") (pinfunction "RESET_DEBUG_RESET_DEBUG") (pintype "bidirectional"))
    )
    (net (code "149") (name "unconnected-(U$1-PadRESET_ICSP)") (class "Default")
      (node (ref "U$1") (pin "RESET_ICSP") (pinfunction "RESET_ICSP_RESET_ICSP") (pintype "bidirectional"))
    )
    (net (code "150") (name "unconnected-(U$1-PadRX0)") (class "Default")
      (node (ref "U$1") (pin "RX0") (pinfunction "RX0_RX0") (pintype "bidirectional"))
    )
    (net (code "151") (name "unconnected-(U$1-PadRX1)") (class "Default")
      (node (ref "U$1") (pin "RX1") (pinfunction "RX1_RX1") (pintype "bidirectional"))
    )
    (net (code "152") (name "unconnected-(U$1-PadRX2)") (class "Default")
      (node (ref "U$1") (pin "RX2") (pinfunction "RX2_RX2") (pintype "bidirectional"))
    )
    (net (code "153") (name "unconnected-(U$1-PadRX3)") (class "Default")
      (node (ref "U$1") (pin "RX3") (pinfunction "RX3_RX3") (pintype "bidirectional"))
    )
    (net (code "154") (name "unconnected-(U$1-PadSCL1)") (class "Default")
      (node (ref "U$1") (pin "SCL1") (pinfunction "SCL1_SCL1") (pintype "bidirectional"))
    )
    (net (code "155") (name "unconnected-(U$1-PadSDA1)") (class "Default")
      (node (ref "U$1") (pin "SDA1") (pinfunction "SDA1_SDA1") (pintype "bidirectional"))
    )
    (net (code "156") (name "unconnected-(U$1-PadSWCLK_DEBUG)") (class "Default")
      (node (ref "U$1") (pin "SWCLK_DEBUG") (pinfunction "SWCLK_DEBUG_SWCLK_DEBUG") (pintype "bidirectional"))
    )
    (net (code "157") (name "unconnected-(U$1-PadSWDIO_DEBUG)") (class "Default")
      (node (ref "U$1") (pin "SWDIO_DEBUG") (pinfunction "SWDIO_DEBUG_SWDIO_DEBUG") (pintype "bidirectional"))
    )
    (net (code "158") (name "unconnected-(U$1-PadTX0)") (class "Default")
      (node (ref "U$1") (pin "TX0") (pinfunction "TX0_TX0") (pintype "bidirectional"))
    )
    (net (code "159") (name "unconnected-(U$1-PadTX1)") (class "Default")
      (node (ref "U$1") (pin "TX1") (pinfunction "TX1_TX1") (pintype "bidirectional"))
    )
    (net (code "160") (name "unconnected-(U$1-PadTX2)") (class "Default")
      (node (ref "U$1") (pin "TX2") (pinfunction "TX2_TX2") (pintype "bidirectional"))
    )
    (net (code "161") (name "unconnected-(U$1-PadTX3)") (class "Default")
      (node (ref "U$1") (pin "TX3") (pinfunction "TX3_TX3") (pintype "bidirectional"))
    )
    (net (code "162") (name "unconnected-(U$1-PadVIN)") (class "Default")
      (node (ref "U$1") (pin "VIN") (pinfunction "VIN_VIN") (pintype "bidirectional"))
    )
  )
)
